# engmon-wroom.net
KiCad netlist of a schematic drawn in EAGLE
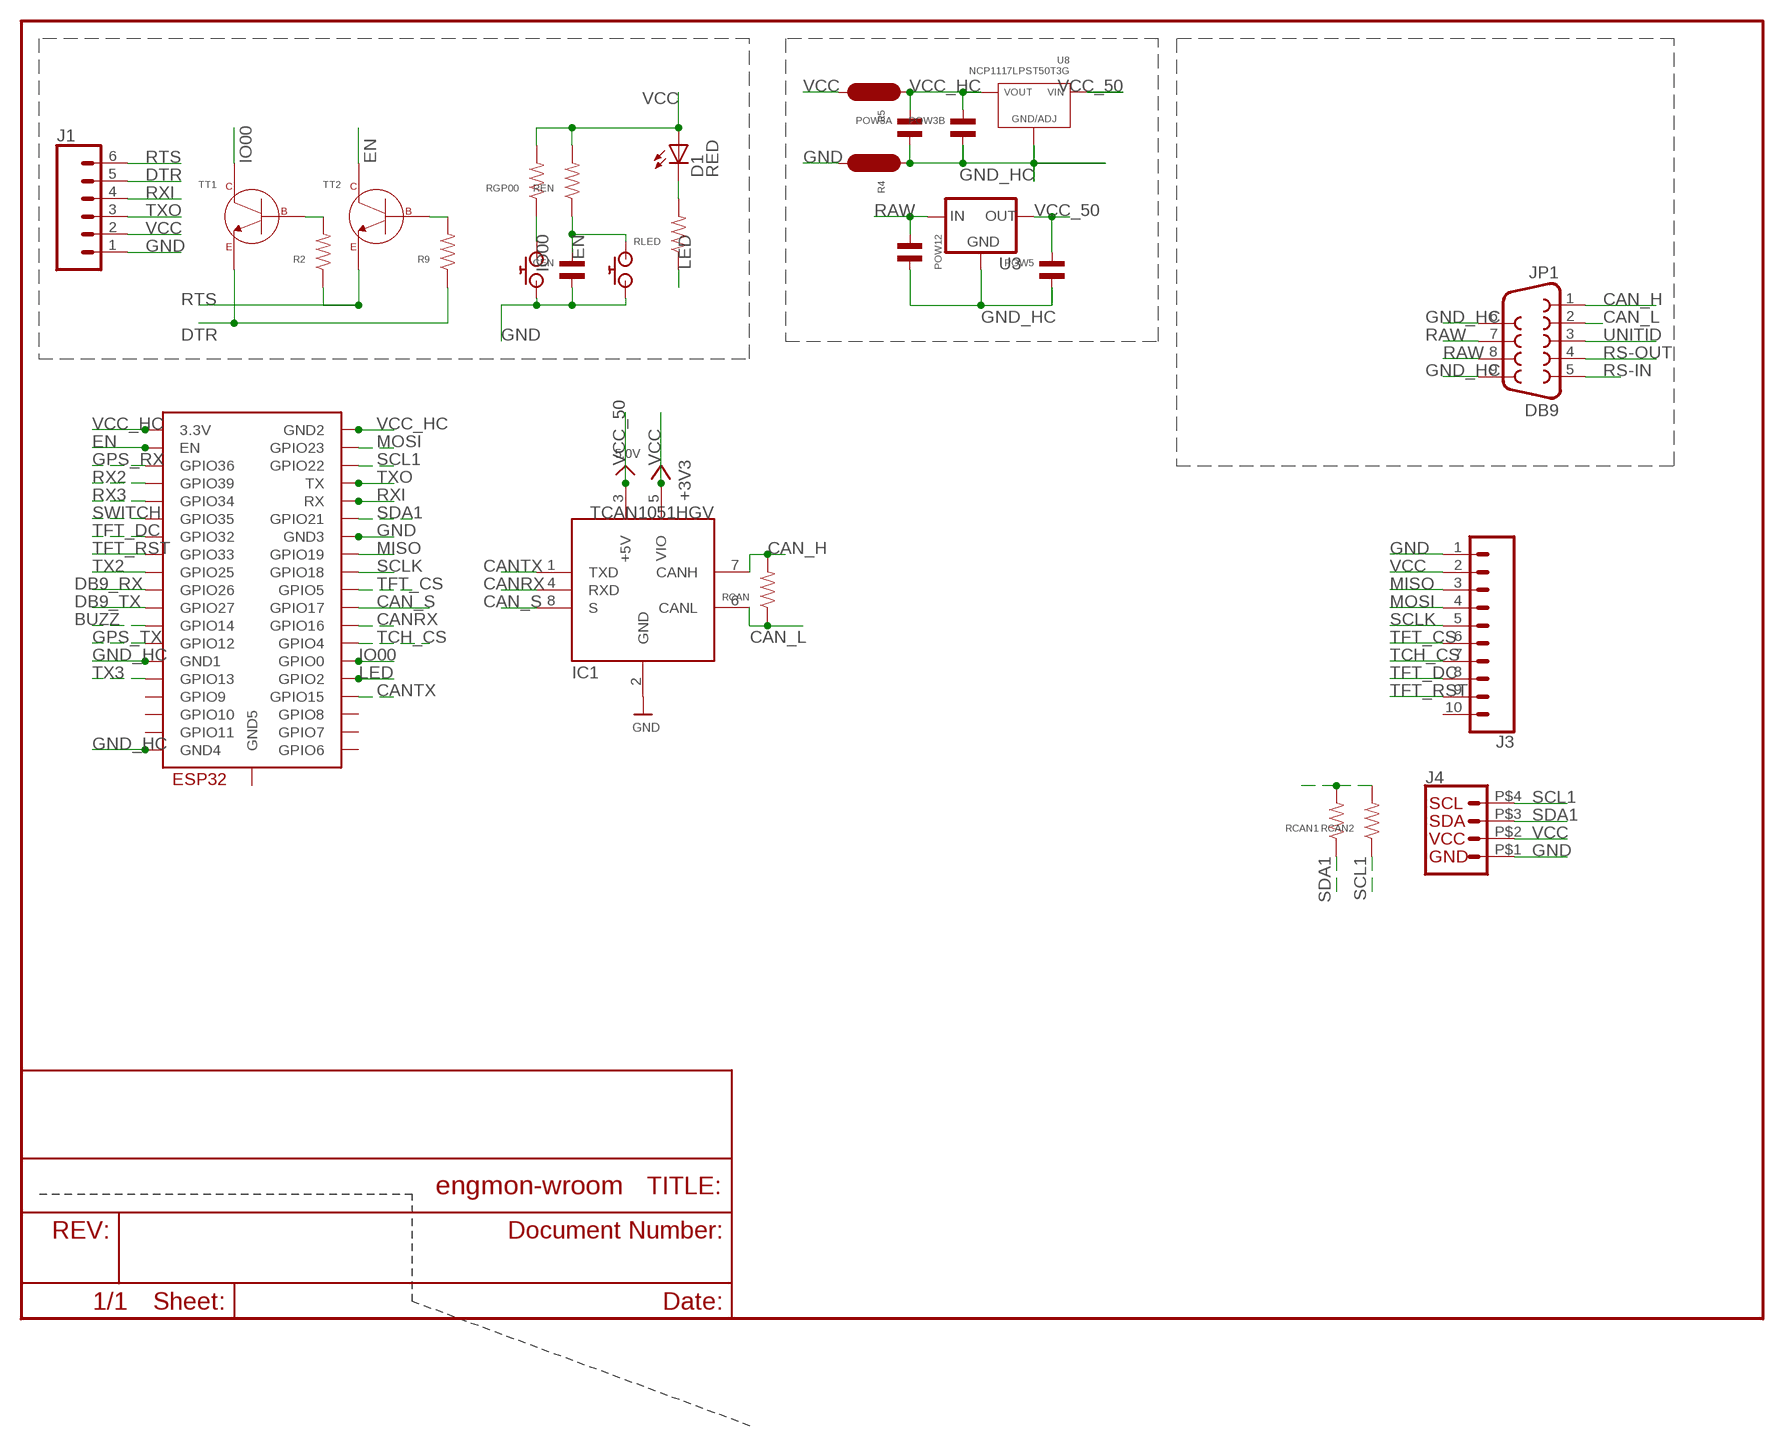
[diagram p0: schematic, sheet 1]

(export (version "E")
  (design (tool "Eeschema 10.0.6"))
  (components
    (comp (ref "CEN")
      (value "CAPACITOR_NP_0603")
      (footprint "eagle-import:C0603")
      (libsource (lib "eagle-import") (part "CAPACITOR_NP_0603"))
    )
    (comp (ref "D1")
      (value "RED")
      (footprint "eagle-import:LED-0603")
      (libsource (lib "eagle-import") (part "LED-RED0603"))
    )
    (comp (ref "IC1")
      (value "TCAN1051HGV")
      (footprint "eagle-import:SOIC8_150MIL")
      (libsource (lib "eagle-import") (part "CAN_TRANSCIEVER_TCAN1051V"))
    )
    (comp (ref "J1")
      (value "CONN_06")
      (footprint "eagle-import:1X6-1.25MM-SMD")
      (libsource (lib "eagle-import") (part "CONN_06"))
    )
    (comp (ref "J3")
      (value "CONN_10")
      (footprint "eagle-import:1X10-1.25MM")
      (libsource (lib "eagle-import") (part "CONN_10"))
    )
    (comp (ref "J4")
      (value "Vertical Qwiic Connector")
      (footprint "eagle-import:JST04_1MM_HOLES")
      (libsource (lib "eagle-import") (part "QWIIC_CONNECTORJST04_1MM_HOLE"))
    )
    (comp (ref "JP1")
      (value "DB9")
      (footprint "eagle-import:DB9")
      (libsource (lib "eagle-import") (part "DB9FEMALE"))
    )
    (comp (ref "POW3A")
      (value "CAPACITOR_NP_0603")
      (footprint "eagle-import:C0603")
      (libsource (lib "eagle-import") (part "CAPACITOR_NP_0603"))
    )
    (comp (ref "POW3B")
      (value "CAPACITOR_NP_0603")
      (footprint "eagle-import:C0603")
      (libsource (lib "eagle-import") (part "CAPACITOR_NP_0603"))
    )
    (comp (ref "POW5")
      (value "CAPACITOR_NP_0603")
      (footprint "eagle-import:C0603")
      (libsource (lib "eagle-import") (part "CAPACITOR_NP_0603"))
    )
    (comp (ref "POW12")
      (value "CAPACITOR_NP_0603")
      (footprint "eagle-import:C0603")
      (libsource (lib "eagle-import") (part "CAPACITOR_NP_0603"))
    )
    (comp (ref "R2")
      (value "RESISTOR_0603")
      (footprint "eagle-import:R0603")
      (libsource (lib "eagle-import") (part "RESISTOR_0603"))
    )
    (comp (ref "R4")
      (value "JUMPER")
      (footprint "eagle-import:R0603_JMP")
      (libsource (lib "eagle-import") (part "JUMPER"))
    )
    (comp (ref "R5")
      (value "JUMPER")
      (footprint "eagle-import:R0603_JMP")
      (libsource (lib "eagle-import") (part "JUMPER"))
    )
    (comp (ref "R9")
      (value "RESISTOR_0603")
      (footprint "eagle-import:R0603")
      (libsource (lib "eagle-import") (part "RESISTOR_0603"))
    )
    (comp (ref "RCAN")
      (value "RESISTOR_0603")
      (footprint "eagle-import:R0603")
      (libsource (lib "eagle-import") (part "RESISTOR_0603"))
    )
    (comp (ref "RCAN1")
      (value "RESISTOR_0603")
      (footprint "eagle-import:R0603")
      (libsource (lib "eagle-import") (part "RESISTOR_0603"))
    )
    (comp (ref "RCAN2")
      (value "RESISTOR_0603")
      (footprint "eagle-import:R0603")
      (libsource (lib "eagle-import") (part "RESISTOR_0603"))
    )
    (comp (ref "REN")
      (value "RESISTOR_0603")
      (footprint "eagle-import:R0603")
      (libsource (lib "eagle-import") (part "RESISTOR_0603"))
    )
    (comp (ref "RGP00")
      (value "RESISTOR_0603")
      (footprint "eagle-import:R0603")
      (libsource (lib "eagle-import") (part "RESISTOR_0603"))
    )
    (comp (ref "RLED")
      (value "RESISTOR_0603")
      (footprint "eagle-import:R0603")
      (libsource (lib "eagle-import") (part "RESISTOR_0603"))
    )
    (comp (ref "TT1")
      (value "MF-DSC-SOT233-MMBT3904")
      (footprint "eagle-import:SOT-23-3")
      (fields (field (name "HOUSEPART") "YES"))
      (libsource (lib "eagle-import") (part "NPN_BJT_SOT-23-3MMBT3904"))
    )
    (comp (ref "TT2")
      (value "MF-DSC-SOT233-MMBT3904")
      (footprint "eagle-import:SOT-23-3")
      (fields (field (name "HOUSEPART") "YES"))
      (libsource (lib "eagle-import") (part "NPN_BJT_SOT-23-3MMBT3904"))
    )
    (comp (ref "U$1")
      (value "AMAZON_BUTTONB2010")
      (footprint "eagle-import:C2010")
      (libsource (lib "eagle-import") (part "AMAZON_BUTTONB2010"))
    )
    (comp (ref "U$2")
      (value "AMAZON_BUTTONB2010")
      (footprint "eagle-import:C2010")
      (libsource (lib "eagle-import") (part "AMAZON_BUTTONB2010"))
    )
    (comp (ref "U$3")
      (value "ESP32-WROOM")
      (footprint "eagle-import:ESP32-WROOM")
      (libsource (lib "eagle-import") (part "ESP32-WROOM"))
    )
    (comp (ref "U3")
      (value "V_REG_78XXSINK")
      (footprint "eagle-import:TO220-IGO")
      (libsource (lib "eagle-import") (part "V_REG_78XXSINK"))
    )
    (comp (ref "U8")
      (value "NCP1117LPST50T3G")
      (footprint "eagle-import:SOT-223-3")
      (fields (field (name "HOUSEPART") "NO"))
      (libsource (lib "eagle-import") (part "NCP1117LPST50T3G"))
    )
  )
  (nets
    (net (code "1") (name "+3V3") (class "Default")
      (node (ref "D1") (pin "A") (pinfunction "A_A") (pintype "passive"))
      (node (ref "IC1") (pin "5") (pinfunction "VIO_5") (pintype "power_in"))
      (node (ref "J1") (pin "2") (pinfunction "2_2") (pintype "passive"))
      (node (ref "J3") (pin "2") (pinfunction "2_2") (pintype "passive"))
      (node (ref "J4") (pin "P$2") (pinfunction "2_P$2") (pintype "power_in"))
      (node (ref "R5") (pin "P$2") (pinfunction "P$2_P$2") (pintype "passive"))
      (node (ref "RCAN1") (pin "P$2") (pinfunction "P$2_P$2") (pintype "passive"))
      (node (ref "RCAN2") (pin "P$2") (pinfunction "P$2_P$2") (pintype "passive"))
      (node (ref "REN") (pin "P$2") (pinfunction "P$2_P$2") (pintype "passive"))
      (node (ref "RGP00") (pin "P$2") (pinfunction "P$2_P$2") (pintype "passive"))
    )
    (net (code "2") (name "/BUZZ") (class "Default")
      (node (ref "U$3") (pin "IO14") (pinfunction "GPIO14_IO14") (pintype "bidirectional"))
    )
    (net (code "3") (name "/CANRX") (class "Default")
      (node (ref "IC1") (pin "4") (pinfunction "RXD_4") (pintype "output"))
      (node (ref "U$3") (pin "IO16") (pinfunction "GPIO16_IO16") (pintype "bidirectional"))
    )
    (net (code "4") (name "/CANTX") (class "Default")
      (node (ref "IC1") (pin "1") (pinfunction "TXD_1") (pintype "input"))
      (node (ref "U$3") (pin "IO15") (pinfunction "GPIO15_IO15") (pintype "bidirectional"))
    )
    (net (code "5") (name "/CAN_H") (class "Default")
      (node (ref "IC1") (pin "7") (pinfunction "CANH_7") (pintype "bidirectional"))
      (node (ref "JP1") (pin "1") (pinfunction "1_1") (pintype "passive"))
      (node (ref "RCAN") (pin "P$2") (pinfunction "P$2_P$2") (pintype "passive"))
    )
    (net (code "6") (name "/CAN_L") (class "Default")
      (node (ref "IC1") (pin "6") (pinfunction "CANL_6") (pintype "bidirectional"))
      (node (ref "JP1") (pin "2") (pinfunction "2_2") (pintype "passive"))
      (node (ref "RCAN") (pin "P$1") (pinfunction "P$1_P$1") (pintype "passive"))
    )
    (net (code "7") (name "/CAN_S") (class "Default")
      (node (ref "IC1") (pin "8") (pinfunction "S_8") (pintype "input"))
      (node (ref "U$3") (pin "IO17") (pinfunction "GPIO17_IO17") (pintype "bidirectional"))
    )
    (net (code "8") (name "/DB9_RX") (class "Default")
      (node (ref "U$3") (pin "IO26") (pinfunction "GPIO26_IO26") (pintype "bidirectional"))
    )
    (net (code "9") (name "/DB9_TX") (class "Default")
      (node (ref "U$3") (pin "IO27") (pinfunction "GPIO27_IO27") (pintype "bidirectional"))
    )
    (net (code "10") (name "/DTR") (class "Default")
      (node (ref "J1") (pin "5") (pinfunction "5_5") (pintype "passive"))
      (node (ref "R9") (pin "P$1") (pinfunction "P$1_P$1") (pintype "passive"))
      (node (ref "TT1") (pin "P$2") (pinfunction "EMITTER_P$2") (pintype "bidirectional"))
    )
    (net (code "11") (name "/EN") (class "Default")
      (node (ref "CEN") (pin "P$1") (pinfunction "P$1_P$1") (pintype "passive"))
      (node (ref "REN") (pin "P$1") (pinfunction "P$1_P$1") (pintype "passive"))
      (node (ref "TT2") (pin "P$3") (pinfunction "COLLECTOR_P$3") (pintype "bidirectional"))
      (node (ref "U$2") (pin "P$1") (pinfunction "P$1_P$1") (pintype "bidirectional"))
      (node (ref "U$3") (pin "EN") (pinfunction "EN_EN") (pintype "bidirectional"))
    )
    (net (code "12") (name "/GND_HC") (class "Default")
      (node (ref "JP1") (pin "6") (pinfunction "6_6") (pintype "passive"))
      (node (ref "JP1") (pin "9") (pinfunction "9_9") (pintype "passive"))
      (node (ref "POW12") (pin "P$2") (pinfunction "P$2_P$2") (pintype "passive"))
      (node (ref "POW3A") (pin "P$2") (pinfunction "P$2_P$2") (pintype "passive"))
      (node (ref "POW3B") (pin "P$2") (pinfunction "P$2_P$2") (pintype "passive"))
      (node (ref "POW5") (pin "P$2") (pinfunction "P$2_P$2") (pintype "passive"))
      (node (ref "R4") (pin "P$1") (pinfunction "P$1_P$1") (pintype "passive"))
      (node (ref "U$3") (pin "GND1") (pinfunction "GND1_GND1") (pintype "bidirectional"))
      (node (ref "U$3") (pin "GND4") (pinfunction "GND4_GND4") (pintype "bidirectional"))
      (node (ref "U3") (pin "GND") (pinfunction "GND_GND") (pintype "input"))
      (node (ref "U8") (pin "P$2") (pinfunction "GND/ADJ_P$2") (pintype "bidirectional"))
    )
    (net (code "13") (name "/GPS_RX") (class "Default")
      (node (ref "U$3") (pin "SENSOR_VP") (pinfunction "GPIO36_SENSOR_VP") (pintype "bidirectional"))
    )
    (net (code "14") (name "/GPS_TX") (class "Default")
      (node (ref "U$3") (pin "IO12") (pinfunction "GPIO12_IO12") (pintype "bidirectional"))
    )
    (net (code "15") (name "/IO00") (class "Default")
      (node (ref "RGP00") (pin "P$1") (pinfunction "P$1_P$1") (pintype "passive"))
      (node (ref "TT1") (pin "P$3") (pinfunction "COLLECTOR_P$3") (pintype "bidirectional"))
      (node (ref "U$1") (pin "P$1") (pinfunction "P$1_P$1") (pintype "bidirectional"))
      (node (ref "U$3") (pin "IO0") (pinfunction "GPIO0_IO0") (pintype "bidirectional"))
    )
    (net (code "16") (name "/LED") (class "Default")
      (node (ref "RLED") (pin "P$1") (pinfunction "P$1_P$1") (pintype "passive"))
      (node (ref "U$3") (pin "IO2") (pinfunction "GPIO2_IO2") (pintype "bidirectional"))
    )
    (net (code "17") (name "/MISO") (class "Default")
      (node (ref "J3") (pin "3") (pinfunction "3_3") (pintype "passive"))
      (node (ref "U$3") (pin "IO19") (pinfunction "GPIO19_IO19") (pintype "bidirectional"))
    )
    (net (code "18") (name "/MOSI") (class "Default")
      (node (ref "J3") (pin "4") (pinfunction "4_4") (pintype "passive"))
      (node (ref "U$3") (pin "IO23") (pinfunction "GPIO23_IO23") (pintype "bidirectional"))
    )
    (net (code "19") (name "/RAW") (class "Default")
      (node (ref "JP1") (pin "7") (pinfunction "7_7") (pintype "passive"))
      (node (ref "JP1") (pin "8") (pinfunction "8_8") (pintype "passive"))
      (node (ref "POW12") (pin "P$1") (pinfunction "P$1_P$1") (pintype "passive"))
      (node (ref "U3") (pin "IN") (pinfunction "IN_IN") (pintype "input"))
    )
    (net (code "20") (name "/RS-IN") (class "Default")
      (node (ref "JP1") (pin "5") (pinfunction "5_5") (pintype "passive"))
    )
    (net (code "21") (name "/RS-OUT") (class "Default")
      (node (ref "JP1") (pin "4") (pinfunction "4_4") (pintype "passive"))
    )
    (net (code "22") (name "/RTS") (class "Default")
      (node (ref "J1") (pin "6") (pinfunction "6_6") (pintype "passive"))
      (node (ref "R2") (pin "P$1") (pinfunction "P$1_P$1") (pintype "passive"))
      (node (ref "TT2") (pin "P$2") (pinfunction "EMITTER_P$2") (pintype "bidirectional"))
    )
    (net (code "23") (name "/RX2") (class "Default")
      (node (ref "U$3") (pin "SENSOR_VN") (pinfunction "GPIO39_SENSOR_VN") (pintype "bidirectional"))
    )
    (net (code "24") (name "/RX3") (class "Default")
      (node (ref "U$3") (pin "IO34") (pinfunction "GPIO34_IO34") (pintype "bidirectional"))
    )
    (net (code "25") (name "/RXI") (class "Default")
      (node (ref "J1") (pin "4") (pinfunction "4_4") (pintype "passive"))
      (node (ref "U$3") (pin "RX") (pinfunction "RX_RX") (pintype "bidirectional"))
    )
    (net (code "26") (name "/SCL1") (class "Default")
      (node (ref "J4") (pin "P$4") (pinfunction "4_P$4") (pintype "passive"))
      (node (ref "RCAN2") (pin "P$1") (pinfunction "P$1_P$1") (pintype "passive"))
      (node (ref "U$3") (pin "IO22") (pinfunction "GPIO22_IO22") (pintype "bidirectional"))
    )
    (net (code "27") (name "/SCLK") (class "Default")
      (node (ref "J3") (pin "5") (pinfunction "5_5") (pintype "passive"))
      (node (ref "U$3") (pin "IO18") (pinfunction "GPIO18_IO18") (pintype "bidirectional"))
    )
    (net (code "28") (name "/SDA1") (class "Default")
      (node (ref "J4") (pin "P$3") (pinfunction "3_P$3") (pintype "passive"))
      (node (ref "RCAN1") (pin "P$1") (pinfunction "P$1_P$1") (pintype "passive"))
      (node (ref "U$3") (pin "IO21") (pinfunction "GPIO21_IO21") (pintype "bidirectional"))
    )
    (net (code "29") (name "/SWITCH") (class "Default")
      (node (ref "U$3") (pin "IO35") (pinfunction "GPIO35_IO35") (pintype "bidirectional"))
    )
    (net (code "30") (name "/TCH_CS") (class "Default")
      (node (ref "J3") (pin "7") (pinfunction "7_7") (pintype "passive"))
      (node (ref "U$3") (pin "IO4") (pinfunction "GPIO4_IO4") (pintype "bidirectional"))
    )
    (net (code "31") (name "/TFT_CS") (class "Default")
      (node (ref "J3") (pin "6") (pinfunction "6_6") (pintype "passive"))
      (node (ref "U$3") (pin "IO5") (pinfunction "GPIO5_IO5") (pintype "bidirectional"))
    )
    (net (code "32") (name "/TFT_DC") (class "Default")
      (node (ref "J3") (pin "8") (pinfunction "8_8") (pintype "passive"))
      (node (ref "U$3") (pin "IO32") (pinfunction "GPIO32_IO32") (pintype "bidirectional"))
    )
    (net (code "33") (name "/TFT_RST") (class "Default")
      (node (ref "J3") (pin "9") (pinfunction "9_9") (pintype "passive"))
      (node (ref "U$3") (pin "IO33") (pinfunction "GPIO33_IO33") (pintype "bidirectional"))
    )
    (net (code "34") (name "/TX2") (class "Default")
      (node (ref "U$3") (pin "IO25") (pinfunction "GPIO25_IO25") (pintype "bidirectional"))
    )
    (net (code "35") (name "/TX3") (class "Default")
      (node (ref "U$3") (pin "IO13") (pinfunction "GPIO13_IO13") (pintype "bidirectional"))
    )
    (net (code "36") (name "/TXO") (class "Default")
      (node (ref "J1") (pin "3") (pinfunction "3_3") (pintype "passive"))
      (node (ref "U$3") (pin "TX") (pinfunction "TX_TX") (pintype "bidirectional"))
    )
    (net (code "37") (name "/UNITID") (class "Default")
      (node (ref "JP1") (pin "3") (pinfunction "3_3") (pintype "passive"))
    )
    (net (code "38") (name "/VCC_HC") (class "Default")
      (node (ref "POW3A") (pin "P$1") (pinfunction "P$1_P$1") (pintype "passive"))
      (node (ref "POW3B") (pin "P$1") (pinfunction "P$1_P$1") (pintype "passive"))
      (node (ref "R5") (pin "P$1") (pinfunction "P$1_P$1") (pintype "passive"))
      (node (ref "U$3") (pin "3V3") (pinfunction "3.3V_3V3") (pintype "bidirectional"))
      (node (ref "U$3") (pin "GND2") (pinfunction "GND2_GND2") (pintype "bidirectional"))
      (node (ref "U8") (pin "P$1") (pinfunction "VOUT_P$1") (pintype "bidirectional"))
      (node (ref "U8") (pin "P$3") (pinfunction "VOUT_P$3") (pintype "bidirectional"))
    )
    (net (code "39") (name "5.0V") (class "Default")
      (node (ref "IC1") (pin "3") (pinfunction "+5V_3") (pintype "power_in"))
      (node (ref "POW5") (pin "P$1") (pinfunction "P$1_P$1") (pintype "passive"))
      (node (ref "U3") (pin "OUT") (pinfunction "OUT_OUT") (pintype "passive"))
      (node (ref "U8") (pin "P$4") (pinfunction "VIN_P$4") (pintype "bidirectional"))
    )
    (net (code "40") (name "GND") (class "Default")
      (node (ref "CEN") (pin "P$2") (pinfunction "P$2_P$2") (pintype "passive"))
      (node (ref "IC1") (pin "2") (pinfunction "GND_2") (pintype "power_in"))
      (node (ref "J1") (pin "1") (pinfunction "1_1") (pintype "passive"))
      (node (ref "J3") (pin "1") (pinfunction "1_1") (pintype "passive"))
      (node (ref "J4") (pin "P$1") (pinfunction "1_P$1") (pintype "power_in"))
      (node (ref "R4") (pin "P$2") (pinfunction "P$2_P$2") (pintype "passive"))
      (node (ref "U$1") (pin "P$2") (pinfunction "P$2_P$2") (pintype "bidirectional"))
      (node (ref "U$2") (pin "P$2") (pinfunction "P$2_P$2") (pintype "bidirectional"))
      (node (ref "U$3") (pin "GND3") (pinfunction "GND3_GND3") (pintype "bidirectional"))
    )
    (net (code "41") (name "Net-(D1-PadC)") (class "Default")
      (node (ref "D1") (pin "C") (pinfunction "C_C") (pintype "passive"))
      (node (ref "RLED") (pin "P$2") (pinfunction "P$2_P$2") (pintype "passive"))
    )
    (net (code "42") (name "Net-(TT1-BASE)") (class "Default")
      (node (ref "R2") (pin "P$2") (pinfunction "P$2_P$2") (pintype "passive"))
      (node (ref "TT1") (pin "P$1") (pinfunction "BASE_P$1") (pintype "bidirectional"))
    )
    (net (code "43") (name "Net-(TT2-BASE)") (class "Default")
      (node (ref "R9") (pin "P$2") (pinfunction "P$2_P$2") (pintype "passive"))
      (node (ref "TT2") (pin "P$1") (pinfunction "BASE_P$1") (pintype "bidirectional"))
    )
    (net (code "44") (name "unconnected-(J3-Pad10)") (class "Default")
      (node (ref "J3") (pin "10") (pinfunction "10_10") (pintype "passive"))
    )
    (net (code "45") (name "unconnected-(U$3-GPIO6-PadCLK)") (class "Default")
      (node (ref "U$3") (pin "CLK") (pinfunction "GPIO6_CLK") (pintype "bidirectional"))
    )
    (net (code "46") (name "unconnected-(U$3-GPIO7-PadSD0)") (class "Default")
      (node (ref "U$3") (pin "SD0") (pinfunction "GPIO7_SD0") (pintype "bidirectional"))
    )
    (net (code "47") (name "unconnected-(U$3-GPIO8-PadSD1)") (class "Default")
      (node (ref "U$3") (pin "SD1") (pinfunction "GPIO8_SD1") (pintype "bidirectional"))
    )
    (net (code "48") (name "unconnected-(U$3-GPIO9-PadSD2)") (class "Default")
      (node (ref "U$3") (pin "SD2") (pinfunction "GPIO9_SD2") (pintype "bidirectional"))
    )
    (net (code "49") (name "unconnected-(U$3-GPIO10-PadSD3)") (class "Default")
      (node (ref "U$3") (pin "SD3") (pinfunction "GPIO10_SD3") (pintype "bidirectional"))
    )
    (net (code "50") (name "unconnected-(U$3-GPIO11-PadCMD)") (class "Default")
      (node (ref "U$3") (pin "CMD") (pinfunction "GPIO11_CMD") (pintype "bidirectional"))
    )
    (net (code "51") (name "unconnected-(U$3-PadGND5)") (class "Default")
      (node (ref "U$3") (pin "GND5") (pinfunction "GND5_GND5") (pintype "bidirectional"))
    )
  )
)
